# DenScript_LDR_V1_0.net
KiCad netlist of a schematic drawn in EAGLE
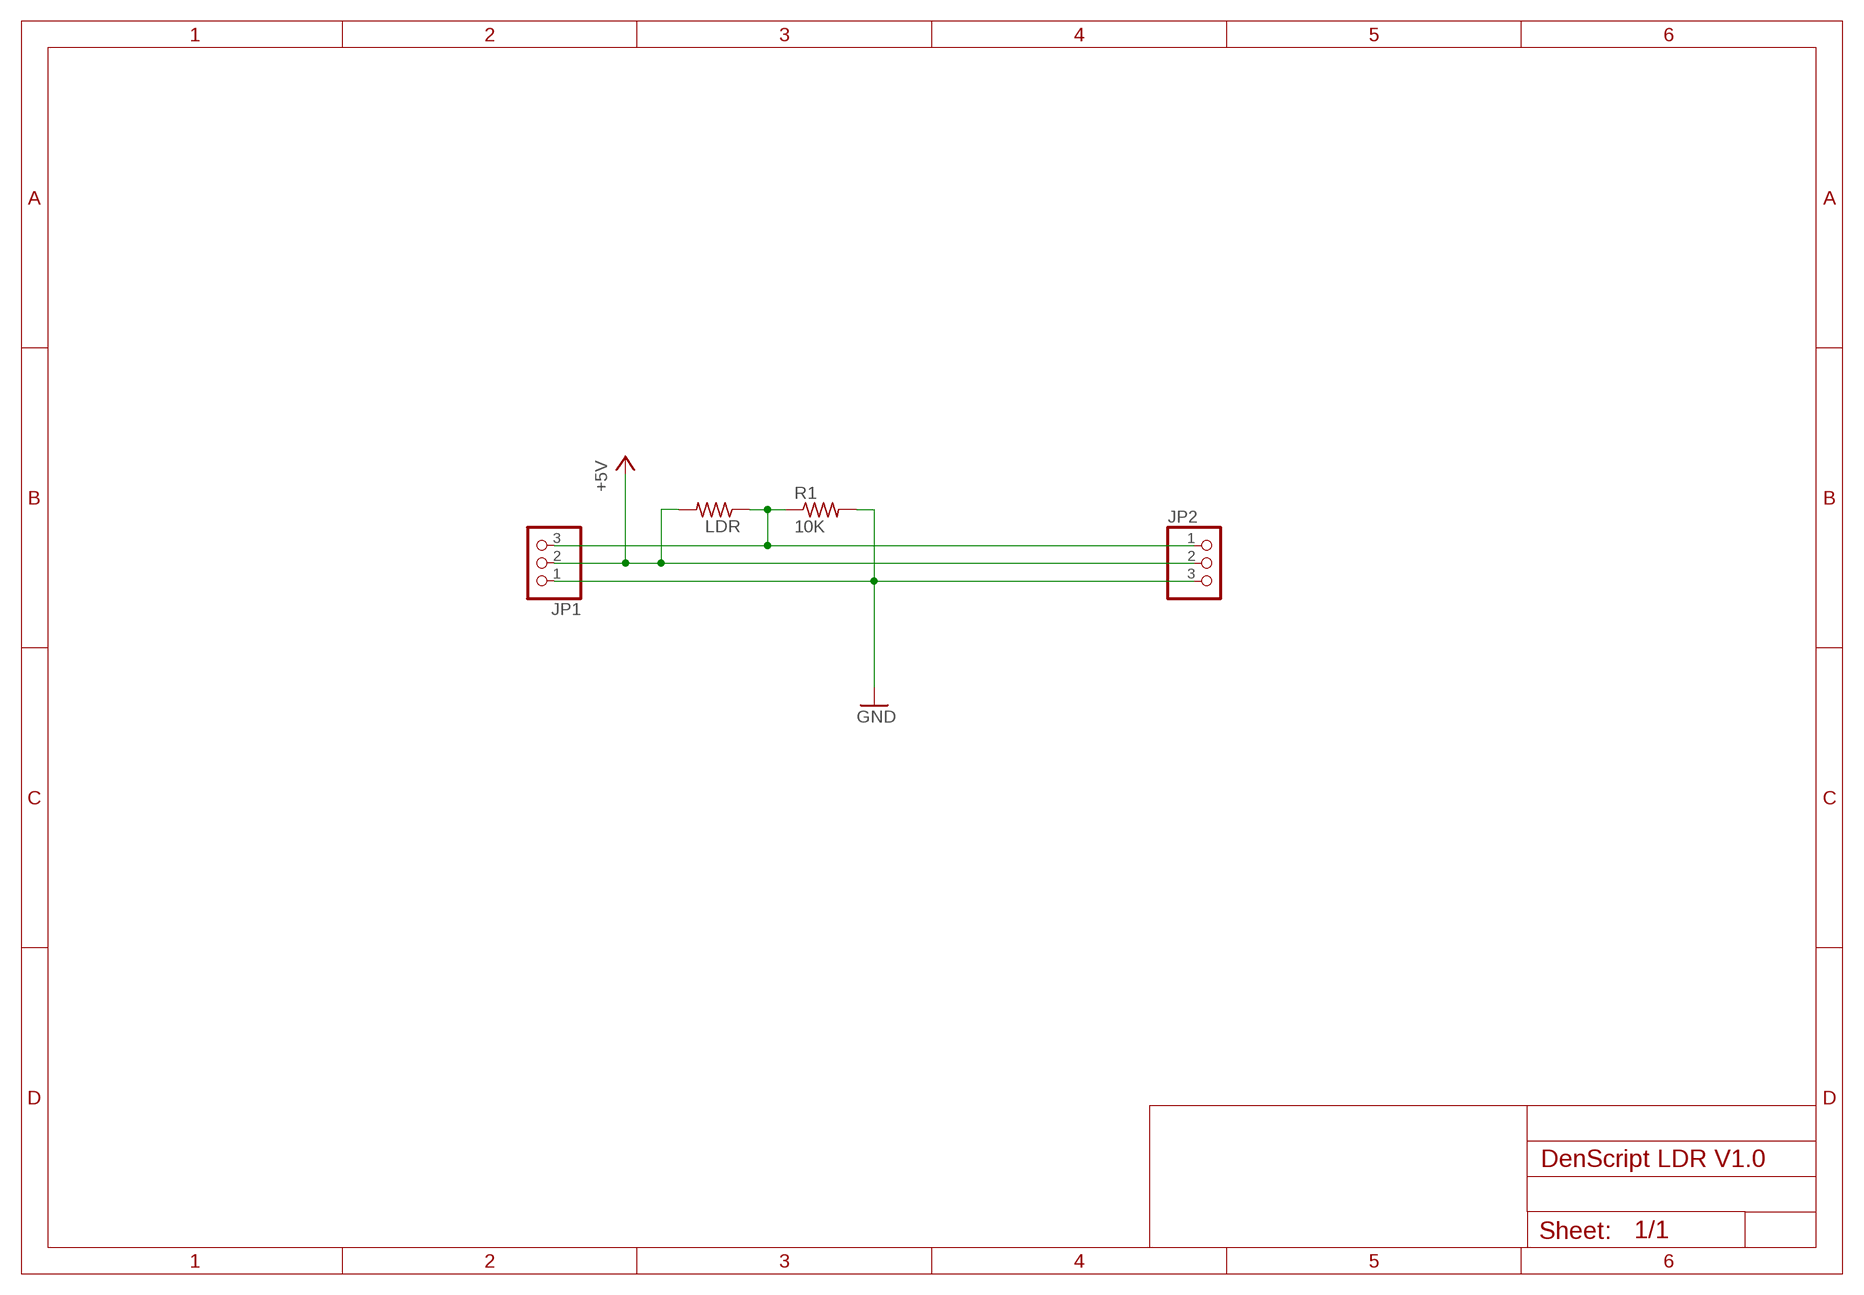
[diagram p0: schematic, sheet 1]

(export (version "E")
  (design (tool "Eeschema 10.0.6"))
  (components
    (comp (ref "JP1")
      (value "PINHD-1X3")
      (footprint "eagle-import:1X03")
      (libsource (lib "eagle-import") (part "PINHD-1X3"))
    )
    (comp (ref "JP2")
      (value "PINHD-1X3")
      (footprint "eagle-import:1X03")
      (libsource (lib "eagle-import") (part "PINHD-1X3"))
    )
    (comp (ref "LDR")
      (value "R-US_0204/5")
      (footprint "eagle-import:0204_5")
      (libsource (lib "eagle-import") (part "R-US_0204/5"))
    )
    (comp (ref "R1")
      (value "10K")
      (footprint "eagle-import:R0603")
      (libsource (lib "eagle-import") (part "R-US_R0603"))
    )
  )
  (nets
    (net (code "1") (name "+5V") (class "Default")
      (node (ref "JP1") (pin "2") (pinfunction "2_2") (pintype "passive"))
      (node (ref "JP2") (pin "2") (pinfunction "2_2") (pintype "passive"))
      (node (ref "LDR") (pin "2") (pinfunction "2_2") (pintype "passive"))
    )
    (net (code "2") (name "GND") (class "Default")
      (node (ref "JP1") (pin "1") (pinfunction "1_1") (pintype "passive"))
      (node (ref "JP2") (pin "3") (pinfunction "3_3") (pintype "passive"))
      (node (ref "R1") (pin "2") (pinfunction "2_2") (pintype "passive"))
    )
    (net (code "3") (name "Net-(JP1-Pad3)") (class "Default")
      (node (ref "JP1") (pin "3") (pinfunction "3_3") (pintype "passive"))
      (node (ref "JP2") (pin "1") (pinfunction "1_1") (pintype "passive"))
      (node (ref "LDR") (pin "1") (pinfunction "1_1") (pintype "passive"))
      (node (ref "R1") (pin "1") (pinfunction "1_1") (pintype "passive"))
    )
  )
)
